# xns-ip67.net
KiCad netlist of a schematic drawn in EAGLE
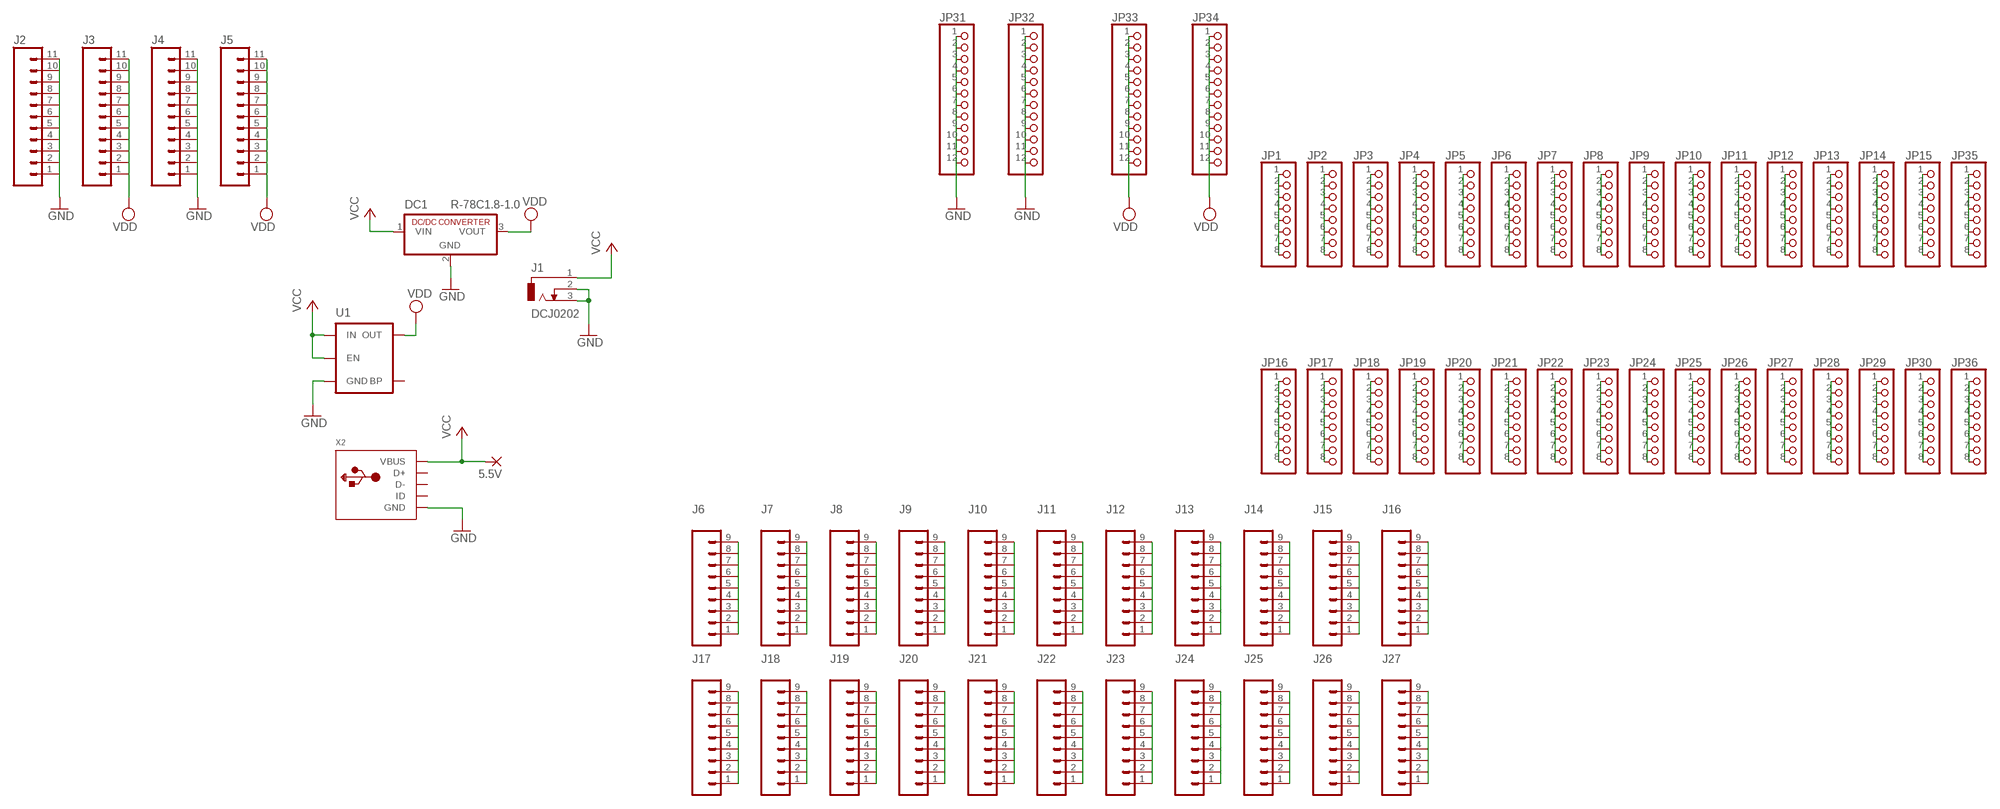
[diagram p0: schematic, sheet 1]

(export (version "E")
  (design (tool "Eeschema 10.0.6"))
  (components
    (comp (ref "5.5V")
      (value "WIREPAD1,6/0,9")
      (footprint "eagle-import:1,6_0,9")
      (libsource (lib "eagle-import") (part "WIREPAD1,6/0,9"))
    )
    (comp (ref "DC1")
      (value "R-78C1.8-1.0")
      (footprint "eagle-import:SIP3")
      (libsource (lib "eagle-import") (part "R-78C-1.01.8"))
    )
    (comp (ref "J1")
      (value "DCJ0202")
      (footprint "eagle-import:DCJ0202")
      (libsource (lib "eagle-import") (part "DCJ0202"))
    )
    (comp (ref "J2")
      (value "M111X11_NO_SILK")
      (footprint "eagle-import:1X11_NO_SILK")
      (libsource (lib "eagle-import") (part "M111X11_NO_SILK"))
    )
    (comp (ref "J3")
      (value "M111X11_NO_SILK")
      (footprint "eagle-import:1X11_NO_SILK")
      (libsource (lib "eagle-import") (part "M111X11_NO_SILK"))
    )
    (comp (ref "J4")
      (value "M111X11_NO_SILK")
      (footprint "eagle-import:1X11_NO_SILK")
      (libsource (lib "eagle-import") (part "M111X11_NO_SILK"))
    )
    (comp (ref "J5")
      (value "M111X11_NO_SILK")
      (footprint "eagle-import:1X11_NO_SILK")
      (libsource (lib "eagle-import") (part "M111X11_NO_SILK"))
    )
    (comp (ref "J6")
      (value "M09NO_SILK")
      (footprint "eagle-import:1X09_NO_SILK")
      (libsource (lib "eagle-import") (part "M09NO_SILK"))
    )
    (comp (ref "J7")
      (value "M09NO_SILK")
      (footprint "eagle-import:1X09_NO_SILK")
      (libsource (lib "eagle-import") (part "M09NO_SILK"))
    )
    (comp (ref "J8")
      (value "M09NO_SILK")
      (footprint "eagle-import:1X09_NO_SILK")
      (libsource (lib "eagle-import") (part "M09NO_SILK"))
    )
    (comp (ref "J9")
      (value "M09NO_SILK")
      (footprint "eagle-import:1X09_NO_SILK")
      (libsource (lib "eagle-import") (part "M09NO_SILK"))
    )
    (comp (ref "J10")
      (value "M09NO_SILK")
      (footprint "eagle-import:1X09_NO_SILK")
      (libsource (lib "eagle-import") (part "M09NO_SILK"))
    )
    (comp (ref "J11")
      (value "M09NO_SILK")
      (footprint "eagle-import:1X09_NO_SILK")
      (libsource (lib "eagle-import") (part "M09NO_SILK"))
    )
    (comp (ref "J12")
      (value "M09NO_SILK")
      (footprint "eagle-import:1X09_NO_SILK")
      (libsource (lib "eagle-import") (part "M09NO_SILK"))
    )
    (comp (ref "J13")
      (value "M09NO_SILK")
      (footprint "eagle-import:1X09_NO_SILK")
      (libsource (lib "eagle-import") (part "M09NO_SILK"))
    )
    (comp (ref "J14")
      (value "M09NO_SILK")
      (footprint "eagle-import:1X09_NO_SILK")
      (libsource (lib "eagle-import") (part "M09NO_SILK"))
    )
    (comp (ref "J15")
      (value "M09NO_SILK")
      (footprint "eagle-import:1X09_NO_SILK")
      (libsource (lib "eagle-import") (part "M09NO_SILK"))
    )
    (comp (ref "J16")
      (value "M09NO_SILK")
      (footprint "eagle-import:1X09_NO_SILK")
      (libsource (lib "eagle-import") (part "M09NO_SILK"))
    )
    (comp (ref "J17")
      (value "M09NO_SILK")
      (footprint "eagle-import:1X09_NO_SILK")
      (libsource (lib "eagle-import") (part "M09NO_SILK"))
    )
    (comp (ref "J18")
      (value "M09NO_SILK")
      (footprint "eagle-import:1X09_NO_SILK")
      (libsource (lib "eagle-import") (part "M09NO_SILK"))
    )
    (comp (ref "J19")
      (value "M09NO_SILK")
      (footprint "eagle-import:1X09_NO_SILK")
      (libsource (lib "eagle-import") (part "M09NO_SILK"))
    )
    (comp (ref "J20")
      (value "M09NO_SILK")
      (footprint "eagle-import:1X09_NO_SILK")
      (libsource (lib "eagle-import") (part "M09NO_SILK"))
    )
    (comp (ref "J21")
      (value "M09NO_SILK")
      (footprint "eagle-import:1X09_NO_SILK")
      (libsource (lib "eagle-import") (part "M09NO_SILK"))
    )
    (comp (ref "J22")
      (value "M09NO_SILK")
      (footprint "eagle-import:1X09_NO_SILK")
      (libsource (lib "eagle-import") (part "M09NO_SILK"))
    )
    (comp (ref "J23")
      (value "M09NO_SILK")
      (footprint "eagle-import:1X09_NO_SILK")
      (libsource (lib "eagle-import") (part "M09NO_SILK"))
    )
    (comp (ref "J24")
      (value "M09NO_SILK")
      (footprint "eagle-import:1X09_NO_SILK")
      (libsource (lib "eagle-import") (part "M09NO_SILK"))
    )
    (comp (ref "J25")
      (value "M09NO_SILK")
      (footprint "eagle-import:1X09_NO_SILK")
      (libsource (lib "eagle-import") (part "M09NO_SILK"))
    )
    (comp (ref "J26")
      (value "M09NO_SILK")
      (footprint "eagle-import:1X09_NO_SILK")
      (libsource (lib "eagle-import") (part "M09NO_SILK"))
    )
    (comp (ref "J27")
      (value "M09NO_SILK")
      (footprint "eagle-import:1X09_NO_SILK")
      (libsource (lib "eagle-import") (part "M09NO_SILK"))
    )
    (comp (ref "JP1")
      (value "PINHD-1X8CLEANBIG")
      (footprint "eagle-import:1X08-CLEANBIG")
      (libsource (lib "eagle-import") (part "PINHD-1X8CLEANBIG"))
    )
    (comp (ref "JP2")
      (value "PINHD-1X8CLEANBIG")
      (footprint "eagle-import:1X08-CLEANBIG")
      (libsource (lib "eagle-import") (part "PINHD-1X8CLEANBIG"))
    )
    (comp (ref "JP3")
      (value "PINHD-1X8CLEANBIG")
      (footprint "eagle-import:1X08-CLEANBIG")
      (libsource (lib "eagle-import") (part "PINHD-1X8CLEANBIG"))
    )
    (comp (ref "JP4")
      (value "PINHD-1X8CLEANBIG")
      (footprint "eagle-import:1X08-CLEANBIG")
      (libsource (lib "eagle-import") (part "PINHD-1X8CLEANBIG"))
    )
    (comp (ref "JP5")
      (value "PINHD-1X8CLEANBIG")
      (footprint "eagle-import:1X08-CLEANBIG")
      (libsource (lib "eagle-import") (part "PINHD-1X8CLEANBIG"))
    )
    (comp (ref "JP6")
      (value "PINHD-1X8CLEANBIG")
      (footprint "eagle-import:1X08-CLEANBIG")
      (libsource (lib "eagle-import") (part "PINHD-1X8CLEANBIG"))
    )
    (comp (ref "JP7")
      (value "PINHD-1X8CLEANBIG")
      (footprint "eagle-import:1X08-CLEANBIG")
      (libsource (lib "eagle-import") (part "PINHD-1X8CLEANBIG"))
    )
    (comp (ref "JP8")
      (value "PINHD-1X8CLEANBIG")
      (footprint "eagle-import:1X08-CLEANBIG")
      (libsource (lib "eagle-import") (part "PINHD-1X8CLEANBIG"))
    )
    (comp (ref "JP9")
      (value "PINHD-1X8CLEANBIG")
      (footprint "eagle-import:1X08-CLEANBIG")
      (libsource (lib "eagle-import") (part "PINHD-1X8CLEANBIG"))
    )
    (comp (ref "JP10")
      (value "PINHD-1X8CLEANBIG")
      (footprint "eagle-import:1X08-CLEANBIG")
      (libsource (lib "eagle-import") (part "PINHD-1X8CLEANBIG"))
    )
    (comp (ref "JP11")
      (value "PINHD-1X8CLEANBIG")
      (footprint "eagle-import:1X08-CLEANBIG")
      (libsource (lib "eagle-import") (part "PINHD-1X8CLEANBIG"))
    )
    (comp (ref "JP12")
      (value "PINHD-1X8CLEANBIG")
      (footprint "eagle-import:1X08-CLEANBIG")
      (libsource (lib "eagle-import") (part "PINHD-1X8CLEANBIG"))
    )
    (comp (ref "JP13")
      (value "PINHD-1X8CLEANBIG")
      (footprint "eagle-import:1X08-CLEANBIG")
      (libsource (lib "eagle-import") (part "PINHD-1X8CLEANBIG"))
    )
    (comp (ref "JP14")
      (value "PINHD-1X8CLEANBIG")
      (footprint "eagle-import:1X08-CLEANBIG")
      (libsource (lib "eagle-import") (part "PINHD-1X8CLEANBIG"))
    )
    (comp (ref "JP15")
      (value "PINHD-1X8CLEANBIG")
      (footprint "eagle-import:1X08-CLEANBIG")
      (libsource (lib "eagle-import") (part "PINHD-1X8CLEANBIG"))
    )
    (comp (ref "JP16")
      (value "PINHD-1X8CLEANBIG")
      (footprint "eagle-import:1X08-CLEANBIG")
      (libsource (lib "eagle-import") (part "PINHD-1X8CLEANBIG"))
    )
    (comp (ref "JP17")
      (value "PINHD-1X8CLEANBIG")
      (footprint "eagle-import:1X08-CLEANBIG")
      (libsource (lib "eagle-import") (part "PINHD-1X8CLEANBIG"))
    )
    (comp (ref "JP18")
      (value "PINHD-1X8CLEANBIG")
      (footprint "eagle-import:1X08-CLEANBIG")
      (libsource (lib "eagle-import") (part "PINHD-1X8CLEANBIG"))
    )
    (comp (ref "JP19")
      (value "PINHD-1X8CLEANBIG")
      (footprint "eagle-import:1X08-CLEANBIG")
      (libsource (lib "eagle-import") (part "PINHD-1X8CLEANBIG"))
    )
    (comp (ref "JP20")
      (value "PINHD-1X8CLEANBIG")
      (footprint "eagle-import:1X08-CLEANBIG")
      (libsource (lib "eagle-import") (part "PINHD-1X8CLEANBIG"))
    )
    (comp (ref "JP21")
      (value "PINHD-1X8CLEANBIG")
      (footprint "eagle-import:1X08-CLEANBIG")
      (libsource (lib "eagle-import") (part "PINHD-1X8CLEANBIG"))
    )
    (comp (ref "JP22")
      (value "PINHD-1X8CLEANBIG")
      (footprint "eagle-import:1X08-CLEANBIG")
      (libsource (lib "eagle-import") (part "PINHD-1X8CLEANBIG"))
    )
    (comp (ref "JP23")
      (value "PINHD-1X8CLEANBIG")
      (footprint "eagle-import:1X08-CLEANBIG")
      (libsource (lib "eagle-import") (part "PINHD-1X8CLEANBIG"))
    )
    (comp (ref "JP24")
      (value "PINHD-1X8CLEANBIG")
      (footprint "eagle-import:1X08-CLEANBIG")
      (libsource (lib "eagle-import") (part "PINHD-1X8CLEANBIG"))
    )
    (comp (ref "JP25")
      (value "PINHD-1X8CLEANBIG")
      (footprint "eagle-import:1X08-CLEANBIG")
      (libsource (lib "eagle-import") (part "PINHD-1X8CLEANBIG"))
    )
    (comp (ref "JP26")
      (value "PINHD-1X8CLEANBIG")
      (footprint "eagle-import:1X08-CLEANBIG")
      (libsource (lib "eagle-import") (part "PINHD-1X8CLEANBIG"))
    )
    (comp (ref "JP27")
      (value "PINHD-1X8CLEANBIG")
      (footprint "eagle-import:1X08-CLEANBIG")
      (libsource (lib "eagle-import") (part "PINHD-1X8CLEANBIG"))
    )
    (comp (ref "JP28")
      (value "PINHD-1X8CLEANBIG")
      (footprint "eagle-import:1X08-CLEANBIG")
      (libsource (lib "eagle-import") (part "PINHD-1X8CLEANBIG"))
    )
    (comp (ref "JP29")
      (value "PINHD-1X8CLEANBIG")
      (footprint "eagle-import:1X08-CLEANBIG")
      (libsource (lib "eagle-import") (part "PINHD-1X8CLEANBIG"))
    )
    (comp (ref "JP30")
      (value "PINHD-1X8CLEANBIG")
      (footprint "eagle-import:1X08-CLEANBIG")
      (libsource (lib "eagle-import") (part "PINHD-1X8CLEANBIG"))
    )
    (comp (ref "JP31")
      (value "HEADER-1X12")
      (footprint "eagle-import:1X12_ROUND")
      (libsource (lib "eagle-import") (part "HEADER-1X12"))
    )
    (comp (ref "JP32")
      (value "HEADER-1X12")
      (footprint "eagle-import:1X12_ROUND")
      (libsource (lib "eagle-import") (part "HEADER-1X12"))
    )
    (comp (ref "JP33")
      (value "HEADER-1X12")
      (footprint "eagle-import:1X12_ROUND")
      (libsource (lib "eagle-import") (part "HEADER-1X12"))
    )
    (comp (ref "JP34")
      (value "HEADER-1X12")
      (footprint "eagle-import:1X12_ROUND")
      (libsource (lib "eagle-import") (part "HEADER-1X12"))
    )
    (comp (ref "JP35")
      (value "PINHD-1X8CLEANBIG")
      (footprint "eagle-import:1X08-CLEANBIG")
      (libsource (lib "eagle-import") (part "PINHD-1X8CLEANBIG"))
    )
    (comp (ref "JP36")
      (value "PINHD-1X8CLEANBIG")
      (footprint "eagle-import:1X08-CLEANBIG")
      (libsource (lib "eagle-import") (part "PINHD-1X8CLEANBIG"))
    )
    (comp (ref "U1")
      (value "MIC52053.3V")
      (footprint "eagle-import:SOT23-5")
      (libsource (lib "eagle-import") (part "MIC52053.3V"))
    )
    (comp (ref "X2")
      (value "USBMICRO_20329")
      (footprint "eagle-import:4UCONN_20329")
      (libsource (lib "eagle-import") (part "USBMICRO_20329"))
    )
  )
  (nets
    (net (code "1") (name "GND") (class "Default")
      (node (ref "DC1") (pin "2") (pinfunction "GND_2") (pintype "passive"))
      (node (ref "J1") (pin "2") (pinfunction "2_2") (pintype "passive"))
      (node (ref "J1") (pin "3") (pinfunction "3_3") (pintype "passive"))
      (node (ref "J2") (pin "1") (pinfunction "1_1") (pintype "passive"))
      (node (ref "J2") (pin "10") (pinfunction "10_10") (pintype "passive"))
      (node (ref "J2") (pin "11") (pinfunction "11_11") (pintype "passive"))
      (node (ref "J2") (pin "2") (pinfunction "2_2") (pintype "passive"))
      (node (ref "J2") (pin "3") (pinfunction "3_3") (pintype "passive"))
      (node (ref "J2") (pin "4") (pinfunction "4_4") (pintype "passive"))
      (node (ref "J2") (pin "5") (pinfunction "5_5") (pintype "passive"))
      (node (ref "J2") (pin "6") (pinfunction "6_6") (pintype "passive"))
      (node (ref "J2") (pin "7") (pinfunction "7_7") (pintype "passive"))
      (node (ref "J2") (pin "8") (pinfunction "8_8") (pintype "passive"))
      (node (ref "J2") (pin "9") (pinfunction "9_9") (pintype "passive"))
      (node (ref "J4") (pin "1") (pinfunction "1_1") (pintype "passive"))
      (node (ref "J4") (pin "10") (pinfunction "10_10") (pintype "passive"))
      (node (ref "J4") (pin "11") (pinfunction "11_11") (pintype "passive"))
      (node (ref "J4") (pin "2") (pinfunction "2_2") (pintype "passive"))
      (node (ref "J4") (pin "3") (pinfunction "3_3") (pintype "passive"))
      (node (ref "J4") (pin "4") (pinfunction "4_4") (pintype "passive"))
      (node (ref "J4") (pin "5") (pinfunction "5_5") (pintype "passive"))
      (node (ref "J4") (pin "6") (pinfunction "6_6") (pintype "passive"))
      (node (ref "J4") (pin "7") (pinfunction "7_7") (pintype "passive"))
      (node (ref "J4") (pin "8") (pinfunction "8_8") (pintype "passive"))
      (node (ref "J4") (pin "9") (pinfunction "9_9") (pintype "passive"))
      (node (ref "JP31") (pin "1") (pinfunction "1_1") (pintype "passive"))
      (node (ref "JP31") (pin "10") (pinfunction "10_10") (pintype "passive"))
      (node (ref "JP31") (pin "11") (pinfunction "11_11") (pintype "passive"))
      (node (ref "JP31") (pin "12") (pinfunction "12_12") (pintype "passive"))
      (node (ref "JP31") (pin "2") (pinfunction "2_2") (pintype "passive"))
      (node (ref "JP31") (pin "3") (pinfunction "3_3") (pintype "passive"))
      (node (ref "JP31") (pin "4") (pinfunction "4_4") (pintype "passive"))
      (node (ref "JP31") (pin "5") (pinfunction "5_5") (pintype "passive"))
      (node (ref "JP31") (pin "6") (pinfunction "6_6") (pintype "passive"))
      (node (ref "JP31") (pin "7") (pinfunction "7_7") (pintype "passive"))
      (node (ref "JP31") (pin "8") (pinfunction "8_8") (pintype "passive"))
      (node (ref "JP31") (pin "9") (pinfunction "9_9") (pintype "passive"))
      (node (ref "JP32") (pin "1") (pinfunction "1_1") (pintype "passive"))
      (node (ref "JP32") (pin "10") (pinfunction "10_10") (pintype "passive"))
      (node (ref "JP32") (pin "11") (pinfunction "11_11") (pintype "passive"))
      (node (ref "JP32") (pin "12") (pinfunction "12_12") (pintype "passive"))
      (node (ref "JP32") (pin "2") (pinfunction "2_2") (pintype "passive"))
      (node (ref "JP32") (pin "3") (pinfunction "3_3") (pintype "passive"))
      (node (ref "JP32") (pin "4") (pinfunction "4_4") (pintype "passive"))
      (node (ref "JP32") (pin "5") (pinfunction "5_5") (pintype "passive"))
      (node (ref "JP32") (pin "6") (pinfunction "6_6") (pintype "passive"))
      (node (ref "JP32") (pin "7") (pinfunction "7_7") (pintype "passive"))
      (node (ref "JP32") (pin "8") (pinfunction "8_8") (pintype "passive"))
      (node (ref "JP32") (pin "9") (pinfunction "9_9") (pintype "passive"))
      (node (ref "U1") (pin "2") (pinfunction "GND_2") (pintype "input"))
      (node (ref "X2") (pin "BASE@1") (pinfunction "GND_BASE@1") (pintype "power_in"))
      (node (ref "X2") (pin "BASE@2") (pinfunction "GND_BASE@2") (pintype "power_in"))
      (node (ref "X2") (pin "GND") (pinfunction "GND_GND") (pintype "power_in"))
      (node (ref "X2") (pin "SPRT@1") (pinfunction "GND_SPRT@1") (pintype "power_in"))
      (node (ref "X2") (pin "SPRT@2") (pinfunction "GND_SPRT@2") (pintype "power_in"))
      (node (ref "X2") (pin "SPRT@3") (pinfunction "GND_SPRT@3") (pintype "power_in"))
      (node (ref "X2") (pin "SPRT@4") (pinfunction "GND_SPRT@4") (pintype "power_in"))
    )
    (net (code "2") (name "Net-(J6-Pad1)") (class "Default")
      (node (ref "J6") (pin "1") (pinfunction "1_1") (pintype "passive"))
      (node (ref "J6") (pin "2") (pinfunction "2_2") (pintype "passive"))
      (node (ref "J6") (pin "3") (pinfunction "3_3") (pintype "passive"))
      (node (ref "J6") (pin "4") (pinfunction "4_4") (pintype "passive"))
      (node (ref "J6") (pin "5") (pinfunction "5_5") (pintype "passive"))
      (node (ref "J6") (pin "6") (pinfunction "6_6") (pintype "passive"))
      (node (ref "J6") (pin "7") (pinfunction "7_7") (pintype "passive"))
      (node (ref "J6") (pin "8") (pinfunction "8_8") (pintype "passive"))
      (node (ref "J6") (pin "9") (pinfunction "9_9") (pintype "passive"))
    )
    (net (code "3") (name "Net-(J7-Pad1)") (class "Default")
      (node (ref "J7") (pin "1") (pinfunction "1_1") (pintype "passive"))
      (node (ref "J7") (pin "2") (pinfunction "2_2") (pintype "passive"))
      (node (ref "J7") (pin "3") (pinfunction "3_3") (pintype "passive"))
      (node (ref "J7") (pin "4") (pinfunction "4_4") (pintype "passive"))
      (node (ref "J7") (pin "5") (pinfunction "5_5") (pintype "passive"))
      (node (ref "J7") (pin "6") (pinfunction "6_6") (pintype "passive"))
      (node (ref "J7") (pin "7") (pinfunction "7_7") (pintype "passive"))
      (node (ref "J7") (pin "8") (pinfunction "8_8") (pintype "passive"))
      (node (ref "J7") (pin "9") (pinfunction "9_9") (pintype "passive"))
    )
    (net (code "4") (name "Net-(J8-Pad1)") (class "Default")
      (node (ref "J8") (pin "1") (pinfunction "1_1") (pintype "passive"))
      (node (ref "J8") (pin "2") (pinfunction "2_2") (pintype "passive"))
      (node (ref "J8") (pin "3") (pinfunction "3_3") (pintype "passive"))
      (node (ref "J8") (pin "4") (pinfunction "4_4") (pintype "passive"))
      (node (ref "J8") (pin "5") (pinfunction "5_5") (pintype "passive"))
      (node (ref "J8") (pin "6") (pinfunction "6_6") (pintype "passive"))
      (node (ref "J8") (pin "7") (pinfunction "7_7") (pintype "passive"))
      (node (ref "J8") (pin "8") (pinfunction "8_8") (pintype "passive"))
      (node (ref "J8") (pin "9") (pinfunction "9_9") (pintype "passive"))
    )
    (net (code "5") (name "Net-(J9-Pad1)") (class "Default")
      (node (ref "J9") (pin "1") (pinfunction "1_1") (pintype "passive"))
      (node (ref "J9") (pin "2") (pinfunction "2_2") (pintype "passive"))
      (node (ref "J9") (pin "3") (pinfunction "3_3") (pintype "passive"))
      (node (ref "J9") (pin "4") (pinfunction "4_4") (pintype "passive"))
      (node (ref "J9") (pin "5") (pinfunction "5_5") (pintype "passive"))
      (node (ref "J9") (pin "6") (pinfunction "6_6") (pintype "passive"))
      (node (ref "J9") (pin "7") (pinfunction "7_7") (pintype "passive"))
      (node (ref "J9") (pin "8") (pinfunction "8_8") (pintype "passive"))
      (node (ref "J9") (pin "9") (pinfunction "9_9") (pintype "passive"))
    )
    (net (code "6") (name "Net-(J10-Pad1)") (class "Default")
      (node (ref "J10") (pin "1") (pinfunction "1_1") (pintype "passive"))
      (node (ref "J10") (pin "2") (pinfunction "2_2") (pintype "passive"))
      (node (ref "J10") (pin "3") (pinfunction "3_3") (pintype "passive"))
      (node (ref "J10") (pin "4") (pinfunction "4_4") (pintype "passive"))
      (node (ref "J10") (pin "5") (pinfunction "5_5") (pintype "passive"))
      (node (ref "J10") (pin "6") (pinfunction "6_6") (pintype "passive"))
      (node (ref "J10") (pin "7") (pinfunction "7_7") (pintype "passive"))
      (node (ref "J10") (pin "8") (pinfunction "8_8") (pintype "passive"))
      (node (ref "J10") (pin "9") (pinfunction "9_9") (pintype "passive"))
    )
    (net (code "7") (name "Net-(J11-Pad1)") (class "Default")
      (node (ref "J11") (pin "1") (pinfunction "1_1") (pintype "passive"))
      (node (ref "J11") (pin "2") (pinfunction "2_2") (pintype "passive"))
      (node (ref "J11") (pin "3") (pinfunction "3_3") (pintype "passive"))
      (node (ref "J11") (pin "4") (pinfunction "4_4") (pintype "passive"))
      (node (ref "J11") (pin "5") (pinfunction "5_5") (pintype "passive"))
      (node (ref "J11") (pin "6") (pinfunction "6_6") (pintype "passive"))
      (node (ref "J11") (pin "7") (pinfunction "7_7") (pintype "passive"))
      (node (ref "J11") (pin "8") (pinfunction "8_8") (pintype "passive"))
      (node (ref "J11") (pin "9") (pinfunction "9_9") (pintype "passive"))
    )
    (net (code "8") (name "Net-(J12-Pad1)") (class "Default")
      (node (ref "J12") (pin "1") (pinfunction "1_1") (pintype "passive"))
      (node (ref "J12") (pin "2") (pinfunction "2_2") (pintype "passive"))
      (node (ref "J12") (pin "3") (pinfunction "3_3") (pintype "passive"))
      (node (ref "J12") (pin "4") (pinfunction "4_4") (pintype "passive"))
      (node (ref "J12") (pin "5") (pinfunction "5_5") (pintype "passive"))
      (node (ref "J12") (pin "6") (pinfunction "6_6") (pintype "passive"))
      (node (ref "J12") (pin "7") (pinfunction "7_7") (pintype "passive"))
      (node (ref "J12") (pin "8") (pinfunction "8_8") (pintype "passive"))
      (node (ref "J12") (pin "9") (pinfunction "9_9") (pintype "passive"))
    )
    (net (code "9") (name "Net-(J13-Pad1)") (class "Default")
      (node (ref "J13") (pin "1") (pinfunction "1_1") (pintype "passive"))
      (node (ref "J13") (pin "2") (pinfunction "2_2") (pintype "passive"))
      (node (ref "J13") (pin "3") (pinfunction "3_3") (pintype "passive"))
      (node (ref "J13") (pin "4") (pinfunction "4_4") (pintype "passive"))
      (node (ref "J13") (pin "5") (pinfunction "5_5") (pintype "passive"))
      (node (ref "J13") (pin "6") (pinfunction "6_6") (pintype "passive"))
      (node (ref "J13") (pin "7") (pinfunction "7_7") (pintype "passive"))
      (node (ref "J13") (pin "8") (pinfunction "8_8") (pintype "passive"))
      (node (ref "J13") (pin "9") (pinfunction "9_9") (pintype "passive"))
    )
    (net (code "10") (name "Net-(J14-Pad1)") (class "Default")
      (node (ref "J14") (pin "1") (pinfunction "1_1") (pintype "passive"))
      (node (ref "J14") (pin "2") (pinfunction "2_2") (pintype "passive"))
      (node (ref "J14") (pin "3") (pinfunction "3_3") (pintype "passive"))
      (node (ref "J14") (pin "4") (pinfunction "4_4") (pintype "passive"))
      (node (ref "J14") (pin "5") (pinfunction "5_5") (pintype "passive"))
      (node (ref "J14") (pin "6") (pinfunction "6_6") (pintype "passive"))
      (node (ref "J14") (pin "7") (pinfunction "7_7") (pintype "passive"))
      (node (ref "J14") (pin "8") (pinfunction "8_8") (pintype "passive"))
      (node (ref "J14") (pin "9") (pinfunction "9_9") (pintype "passive"))
    )
    (net (code "11") (name "Net-(J15-Pad1)") (class "Default")
      (node (ref "J15") (pin "1") (pinfunction "1_1") (pintype "passive"))
      (node (ref "J15") (pin "2") (pinfunction "2_2") (pintype "passive"))
      (node (ref "J15") (pin "3") (pinfunction "3_3") (pintype "passive"))
      (node (ref "J15") (pin "4") (pinfunction "4_4") (pintype "passive"))
      (node (ref "J15") (pin "5") (pinfunction "5_5") (pintype "passive"))
      (node (ref "J15") (pin "6") (pinfunction "6_6") (pintype "passive"))
      (node (ref "J15") (pin "7") (pinfunction "7_7") (pintype "passive"))
      (node (ref "J15") (pin "8") (pinfunction "8_8") (pintype "passive"))
      (node (ref "J15") (pin "9") (pinfunction "9_9") (pintype "passive"))
    )
    (net (code "12") (name "Net-(J16-Pad1)") (class "Default")
      (node (ref "J16") (pin "1") (pinfunction "1_1") (pintype "passive"))
      (node (ref "J16") (pin "2") (pinfunction "2_2") (pintype "passive"))
      (node (ref "J16") (pin "3") (pinfunction "3_3") (pintype "passive"))
      (node (ref "J16") (pin "4") (pinfunction "4_4") (pintype "passive"))
      (node (ref "J16") (pin "5") (pinfunction "5_5") (pintype "passive"))
      (node (ref "J16") (pin "6") (pinfunction "6_6") (pintype "passive"))
      (node (ref "J16") (pin "7") (pinfunction "7_7") (pintype "passive"))
      (node (ref "J16") (pin "8") (pinfunction "8_8") (pintype "passive"))
      (node (ref "J16") (pin "9") (pinfunction "9_9") (pintype "passive"))
    )
    (net (code "13") (name "Net-(J17-Pad1)") (class "Default")
      (node (ref "J17") (pin "1") (pinfunction "1_1") (pintype "passive"))
      (node (ref "J17") (pin "2") (pinfunction "2_2") (pintype "passive"))
      (node (ref "J17") (pin "3") (pinfunction "3_3") (pintype "passive"))
      (node (ref "J17") (pin "4") (pinfunction "4_4") (pintype "passive"))
      (node (ref "J17") (pin "5") (pinfunction "5_5") (pintype "passive"))
      (node (ref "J17") (pin "6") (pinfunction "6_6") (pintype "passive"))
      (node (ref "J17") (pin "7") (pinfunction "7_7") (pintype "passive"))
      (node (ref "J17") (pin "8") (pinfunction "8_8") (pintype "passive"))
      (node (ref "J17") (pin "9") (pinfunction "9_9") (pintype "passive"))
    )
    (net (code "14") (name "Net-(J18-Pad1)") (class "Default")
      (node (ref "J18") (pin "1") (pinfunction "1_1") (pintype "passive"))
      (node (ref "J18") (pin "2") (pinfunction "2_2") (pintype "passive"))
      (node (ref "J18") (pin "3") (pinfunction "3_3") (pintype "passive"))
      (node (ref "J18") (pin "4") (pinfunction "4_4") (pintype "passive"))
      (node (ref "J18") (pin "5") (pinfunction "5_5") (pintype "passive"))
      (node (ref "J18") (pin "6") (pinfunction "6_6") (pintype "passive"))
      (node (ref "J18") (pin "7") (pinfunction "7_7") (pintype "passive"))
      (node (ref "J18") (pin "8") (pinfunction "8_8") (pintype "passive"))
      (node (ref "J18") (pin "9") (pinfunction "9_9") (pintype "passive"))
    )
    (net (code "15") (name "Net-(J19-Pad1)") (class "Default")
      (node (ref "J19") (pin "1") (pinfunction "1_1") (pintype "passive"))
      (node (ref "J19") (pin "2") (pinfunction "2_2") (pintype "passive"))
      (node (ref "J19") (pin "3") (pinfunction "3_3") (pintype "passive"))
      (node (ref "J19") (pin "4") (pinfunction "4_4") (pintype "passive"))
      (node (ref "J19") (pin "5") (pinfunction "5_5") (pintype "passive"))
      (node (ref "J19") (pin "6") (pinfunction "6_6") (pintype "passive"))
      (node (ref "J19") (pin "7") (pinfunction "7_7") (pintype "passive"))
      (node (ref "J19") (pin "8") (pinfunction "8_8") (pintype "passive"))
      (node (ref "J19") (pin "9") (pinfunction "9_9") (pintype "passive"))
    )
    (net (code "16") (name "Net-(J20-Pad1)") (class "Default")
      (node (ref "J20") (pin "1") (pinfunction "1_1") (pintype "passive"))
      (node (ref "J20") (pin "2") (pinfunction "2_2") (pintype "passive"))
      (node (ref "J20") (pin "3") (pinfunction "3_3") (pintype "passive"))
      (node (ref "J20") (pin "4") (pinfunction "4_4") (pintype "passive"))
      (node (ref "J20") (pin "5") (pinfunction "5_5") (pintype "passive"))
      (node (ref "J20") (pin "6") (pinfunction "6_6") (pintype "passive"))
      (node (ref "J20") (pin "7") (pinfunction "7_7") (pintype "passive"))
      (node (ref "J20") (pin "8") (pinfunction "8_8") (pintype "passive"))
      (node (ref "J20") (pin "9") (pinfunction "9_9") (pintype "passive"))
    )
    (net (code "17") (name "Net-(J21-Pad1)") (class "Default")
      (node (ref "J21") (pin "1") (pinfunction "1_1") (pintype "passive"))
      (node (ref "J21") (pin "2") (pinfunction "2_2") (pintype "passive"))
      (node (ref "J21") (pin "3") (pinfunction "3_3") (pintype "passive"))
      (node (ref "J21") (pin "4") (pinfunction "4_4") (pintype "passive"))
      (node (ref "J21") (pin "5") (pinfunction "5_5") (pintype "passive"))
      (node (ref "J21") (pin "6") (pinfunction "6_6") (pintype "passive"))
      (node (ref "J21") (pin "7") (pinfunction "7_7") (pintype "passive"))
      (node (ref "J21") (pin "8") (pinfunction "8_8") (pintype "passive"))
      (node (ref "J21") (pin "9") (pinfunction "9_9") (pintype "passive"))
    )
    (net (code "18") (name "Net-(J22-Pad1)") (class "Default")
      (node (ref "J22") (pin "1") (pinfunction "1_1") (pintype "passive"))
      (node (ref "J22") (pin "2") (pinfunction "2_2") (pintype "passive"))
      (node (ref "J22") (pin "3") (pinfunction "3_3") (pintype "passive"))
      (node (ref "J22") (pin "4") (pinfunction "4_4") (pintype "passive"))
      (node (ref "J22") (pin "5") (pinfunction "5_5") (pintype "passive"))
      (node (ref "J22") (pin "6") (pinfunction "6_6") (pintype "passive"))
      (node (ref "J22") (pin "7") (pinfunction "7_7") (pintype "passive"))
      (node (ref "J22") (pin "8") (pinfunction "8_8") (pintype "passive"))
      (node (ref "J22") (pin "9") (pinfunction "9_9") (pintype "passive"))
    )
    (net (code "19") (name "Net-(J23-Pad1)") (class "Default")
      (node (ref "J23") (pin "1") (pinfunction "1_1") (pintype "passive"))
      (node (ref "J23") (pin "2") (pinfunction "2_2") (pintype "passive"))
      (node (ref "J23") (pin "3") (pinfunction "3_3") (pintype "passive"))
      (node (ref "J23") (pin "4") (pinfunction "4_4") (pintype "passive"))
      (node (ref "J23") (pin "5") (pinfunction "5_5") (pintype "passive"))
      (node (ref "J23") (pin "6") (pinfunction "6_6") (pintype "passive"))
      (node (ref "J23") (pin "7") (pinfunction "7_7") (pintype "passive"))
      (node (ref "J23") (pin "8") (pinfunction "8_8") (pintype "passive"))
      (node (ref "J23") (pin "9") (pinfunction "9_9") (pintype "passive"))
    )
    (net (code "20") (name "Net-(J24-Pad1)") (class "Default")
      (node (ref "J24") (pin "1") (pinfunction "1_1") (pintype "passive"))
      (node (ref "J24") (pin "2") (pinfunction "2_2") (pintype "passive"))
      (node (ref "J24") (pin "3") (pinfunction "3_3") (pintype "passive"))
      (node (ref "J24") (pin "4") (pinfunction "4_4") (pintype "passive"))
      (node (ref "J24") (pin "5") (pinfunction "5_5") (pintype "passive"))
      (node (ref "J24") (pin "6") (pinfunction "6_6") (pintype "passive"))
      (node (ref "J24") (pin "7") (pinfunction "7_7") (pintype "passive"))
      (node (ref "J24") (pin "8") (pinfunction "8_8") (pintype "passive"))
      (node (ref "J24") (pin "9") (pinfunction "9_9") (pintype "passive"))
    )
    (net (code "21") (name "Net-(J25-Pad1)") (class "Default")
      (node (ref "J25") (pin "1") (pinfunction "1_1") (pintype "passive"))
      (node (ref "J25") (pin "2") (pinfunction "2_2") (pintype "passive"))
      (node (ref "J25") (pin "3") (pinfunction "3_3") (pintype "passive"))
      (node (ref "J25") (pin "4") (pinfunction "4_4") (pintype "passive"))
      (node (ref "J25") (pin "5") (pinfunction "5_5") (pintype "passive"))
      (node (ref "J25") (pin "6") (pinfunction "6_6") (pintype "passive"))
      (node (ref "J25") (pin "7") (pinfunction "7_7") (pintype "passive"))
      (node (ref "J25") (pin "8") (pinfunction "8_8") (pintype "passive"))
      (node (ref "J25") (pin "9") (pinfunction "9_9") (pintype "passive"))
    )
    (net (code "22") (name "Net-(J26-Pad1)") (class "Default")
      (node (ref "J26") (pin "1") (pinfunction "1_1") (pintype "passive"))
      (node (ref "J26") (pin "2") (pinfunction "2_2") (pintype "passive"))
      (node (ref "J26") (pin "3") (pinfunction "3_3") (pintype "passive"))
      (node (ref "J26") (pin "4") (pinfunction "4_4") (pintype "passive"))
      (node (ref "J26") (pin "5") (pinfunction "5_5") (pintype "passive"))
      (node (ref "J26") (pin "6") (pinfunction "6_6") (pintype "passive"))
      (node (ref "J26") (pin "7") (pinfunction "7_7") (pintype "passive"))
      (node (ref "J26") (pin "8") (pinfunction "8_8") (pintype "passive"))
      (node (ref "J26") (pin "9") (pinfunction "9_9") (pintype "passive"))
    )
    (net (code "23") (name "Net-(J27-Pad1)") (class "Default")
      (node (ref "J27") (pin "1") (pinfunction "1_1") (pintype "passive"))
      (node (ref "J27") (pin "2") (pinfunction "2_2") (pintype "passive"))
      (node (ref "J27") (pin "3") (pinfunction "3_3") (pintype "passive"))
      (node (ref "J27") (pin "4") (pinfunction "4_4") (pintype "passive"))
      (node (ref "J27") (pin "5") (pinfunction "5_5") (pintype "passive"))
      (node (ref "J27") (pin "6") (pinfunction "6_6") (pintype "passive"))
      (node (ref "J27") (pin "7") (pinfunction "7_7") (pintype "passive"))
      (node (ref "J27") (pin "8") (pinfunction "8_8") (pintype "passive"))
      (node (ref "J27") (pin "9") (pinfunction "9_9") (pintype "passive"))
    )
    (net (code "24") (name "Net-(JP1-Pad1)") (class "Default")
      (node (ref "JP1") (pin "1") (pinfunction "1_1") (pintype "passive"))
      (node (ref "JP1") (pin "2") (pinfunction "2_2") (pintype "passive"))
      (node (ref "JP1") (pin "3") (pinfunction "3_3") (pintype "passive"))
      (node (ref "JP1") (pin "4") (pinfunction "4_4") (pintype "passive"))
      (node (ref "JP1") (pin "5") (pinfunction "5_5") (pintype "passive"))
      (node (ref "JP1") (pin "6") (pinfunction "6_6") (pintype "passive"))
      (node (ref "JP1") (pin "7") (pinfunction "7_7") (pintype "passive"))
      (node (ref "JP1") (pin "8") (pinfunction "8_8") (pintype "passive"))
    )
    (net (code "25") (name "Net-(JP2-Pad1)") (class "Default")
      (node (ref "JP2") (pin "1") (pinfunction "1_1") (pintype "passive"))
      (node (ref "JP2") (pin "2") (pinfunction "2_2") (pintype "passive"))
      (node (ref "JP2") (pin "3") (pinfunction "3_3") (pintype "passive"))
      (node (ref "JP2") (pin "4") (pinfunction "4_4") (pintype "passive"))
      (node (ref "JP2") (pin "5") (pinfunction "5_5") (pintype "passive"))
      (node (ref "JP2") (pin "6") (pinfunction "6_6") (pintype "passive"))
      (node (ref "JP2") (pin "7") (pinfunction "7_7") (pintype "passive"))
      (node (ref "JP2") (pin "8") (pinfunction "8_8") (pintype "passive"))
    )
    (net (code "26") (name "Net-(JP3-Pad1)") (class "Default")
      (node (ref "JP3") (pin "1") (pinfunction "1_1") (pintype "passive"))
      (node (ref "JP3") (pin "2") (pinfunction "2_2") (pintype "passive"))
      (node (ref "JP3") (pin "3") (pinfunction "3_3") (pintype "passive"))
      (node (ref "JP3") (pin "4") (pinfunction "4_4") (pintype "passive"))
      (node (ref "JP3") (pin "5") (pinfunction "5_5") (pintype "passive"))
      (node (ref "JP3") (pin "6") (pinfunction "6_6") (pintype "passive"))
      (node (ref "JP3") (pin "7") (pinfunction "7_7") (pintype "passive"))
      (node (ref "JP3") (pin "8") (pinfunction "8_8") (pintype "passive"))
    )
    (net (code "27") (name "Net-(JP4-Pad1)") (class "Default")
      (node (ref "JP4") (pin "1") (pinfunction "1_1") (pintype "passive"))
      (node (ref "JP4") (pin "2") (pinfunction "2_2") (pintype "passive"))
      (node (ref "JP4") (pin "3") (pinfunction "3_3") (pintype "passive"))
      (node (ref "JP4") (pin "4") (pinfunction "4_4") (pintype "passive"))
      (node (ref "JP4") (pin "5") (pinfunction "5_5") (pintype "passive"))
      (node (ref "JP4") (pin "6") (pinfunction "6_6") (pintype "passive"))
      (node (ref "JP4") (pin "7") (pinfunction "7_7") (pintype "passive"))
      (node (ref "JP4") (pin "8") (pinfunction "8_8") (pintype "passive"))
    )
    (net (code "28") (name "Net-(JP5-Pad1)") (class "Default")
      (node (ref "JP5") (pin "1") (pinfunction "1_1") (pintype "passive"))
      (node (ref "JP5") (pin "2") (pinfunction "2_2") (pintype "passive"))
      (node (ref "JP5") (pin "3") (pinfunction "3_3") (pintype "passive"))
      (node (ref "JP5") (pin "4") (pinfunction "4_4") (pintype "passive"))
      (node (ref "JP5") (pin "5") (pinfunction "5_5") (pintype "passive"))
      (node (ref "JP5") (pin "6") (pinfunction "6_6") (pintype "passive"))
      (node (ref "JP5") (pin "7") (pinfunction "7_7") (pintype "passive"))
      (node (ref "JP5") (pin "8") (pinfunction "8_8") (pintype "passive"))
    )
    (net (code "29") (name "Net-(JP6-Pad1)") (class "Default")
      (node (ref "JP6") (pin "1") (pinfunction "1_1") (pintype "passive"))
      (node (ref "JP6") (pin "2") (pinfunction "2_2") (pintype "passive"))
      (node (ref "JP6") (pin "3") (pinfunction "3_3") (pintype "passive"))
      (node (ref "JP6") (pin "4") (pinfunction "4_4") (pintype "passive"))
      (node (ref "JP6") (pin "5") (pinfunction "5_5") (pintype "passive"))
      (node (ref "JP6") (pin "6") (pinfunction "6_6") (pintype "passive"))
      (node (ref "JP6") (pin "7") (pinfunction "7_7") (pintype "passive"))
      (node (ref "JP6") (pin "8") (pinfunction "8_8") (pintype "passive"))
    )
    (net (code "30") (name "Net-(JP7-Pad1)") (class "Default")
      (node (ref "JP7") (pin "1") (pinfunction "1_1") (pintype "passive"))
      (node (ref "JP7") (pin "2") (pinfunction "2_2") (pintype "passive"))
      (node (ref "JP7") (pin "3") (pinfunction "3_3") (pintype "passive"))
      (node (ref "JP7") (pin "4") (pinfunction "4_4") (pintype "passive"))
      (node (ref "JP7") (pin "5") (pinfunction "5_5") (pintype "passive"))
      (node (ref "JP7") (pin "6") (pinfunction "6_6") (pintype "passive"))
      (node (ref "JP7") (pin "7") (pinfunction "7_7") (pintype "passive"))
      (node (ref "JP7") (pin "8") (pinfunction "8_8") (pintype "passive"))
    )
    (net (code "31") (name "Net-(JP8-Pad1)") (class "Default")
      (node (ref "JP8") (pin "1") (pinfunction "1_1") (pintype "passive"))
      (node (ref "JP8") (pin "2") (pinfunction "2_2") (pintype "passive"))
      (node (ref "JP8") (pin "3") (pinfunction "3_3") (pintype "passive"))
      (node (ref "JP8") (pin "4") (pinfunction "4_4") (pintype "passive"))
      (node (ref "JP8") (pin "5") (pinfunction "5_5") (pintype "passive"))
      (node (ref "JP8") (pin "6") (pinfunction "6_6") (pintype "passive"))
      (node (ref "JP8") (pin "7") (pinfunction "7_7") (pintype "passive"))
      (node (ref "JP8") (pin "8") (pinfunction "8_8") (pintype "passive"))
    )
    (net (code "32") (name "Net-(JP9-Pad1)") (class "Default")
      (node (ref "JP9") (pin "1") (pinfunction "1_1") (pintype "passive"))
      (node (ref "JP9") (pin "2") (pinfunction "2_2") (pintype "passive"))
      (node (ref "JP9") (pin "3") (pinfunction "3_3") (pintype "passive"))
      (node (ref "JP9") (pin "4") (pinfunction "4_4") (pintype "passive"))
      (node (ref "JP9") (pin "5") (pinfunction "5_5") (pintype "passive"))
      (node (ref "JP9") (pin "6") (pinfunction "6_6") (pintype "passive"))
      (node (ref "JP9") (pin "7") (pinfunction "7_7") (pintype "passive"))
      (node (ref "JP9") (pin "8") (pinfunction "8_8") (pintype "passive"))
    )
    (net (code "33") (name "Net-(JP10-Pad1)") (class "Default")
      (node (ref "JP10") (pin "1") (pinfunction "1_1") (pintype "passive"))
      (node (ref "JP10") (pin "2") (pinfunction "2_2") (pintype "passive"))
      (node (ref "JP10") (pin "3") (pinfunction "3_3") (pintype "passive"))
      (node (ref "JP10") (pin "4") (pinfunction "4_4") (pintype "passive"))
      (node (ref "JP10") (pin "5") (pinfunction "5_5") (pintype "passive"))
      (node (ref "JP10") (pin "6") (pinfunction "6_6") (pintype "passive"))
      (node (ref "JP10") (pin "7") (pinfunction "7_7") (pintype "passive"))
      (node (ref "JP10") (pin "8") (pinfunction "8_8") (pintype "passive"))
    )
    (net (code "34") (name "Net-(JP11-Pad1)") (class "Default")
      (node (ref "JP11") (pin "1") (pinfunction "1_1") (pintype "passive"))
      (node (ref "JP11") (pin "2") (pinfunction "2_2") (pintype "passive"))
      (node (ref "JP11") (pin "3") (pinfunction "3_3") (pintype "passive"))
      (node (ref "JP11") (pin "4") (pinfunction "4_4") (pintype "passive"))
      (node (ref "JP11") (pin "5") (pinfunction "5_5") (pintype "passive"))
      (node (ref "JP11") (pin "6") (pinfunction "6_6") (pintype "passive"))
      (node (ref "JP11") (pin "7") (pinfunction "7_7") (pintype "passive"))
      (node (ref "JP11") (pin "8") (pinfunction "8_8") (pintype "passive"))
    )
    (net (code "35") (name "Net-(JP12-Pad1)") (class "Default")
      (node (ref "JP12") (pin "1") (pinfunction "1_1") (pintype "passive"))
      (node (ref "JP12") (pin "2") (pinfunction "2_2") (pintype "passive"))
      (node (ref "JP12") (pin "3") (pinfunction "3_3") (pintype "passive"))
      (node (ref "JP12") (pin "4") (pinfunction "4_4") (pintype "passive"))
      (node (ref "JP12") (pin "5") (pinfunction "5_5") (pintype "passive"))
      (node (ref "JP12") (pin "6") (pinfunction "6_6") (pintype "passive"))
      (node (ref "JP12") (pin "7") (pinfunction "7_7") (pintype "passive"))
      (node (ref "JP12") (pin "8") (pinfunction "8_8") (pintype "passive"))
    )
    (net (code "36") (name "Net-(JP13-Pad1)") (class "Default")
      (node (ref "JP13") (pin "1") (pinfunction "1_1") (pintype "passive"))
      (node (ref "JP13") (pin "2") (pinfunction "2_2") (pintype "passive"))
      (node (ref "JP13") (pin "3") (pinfunction "3_3") (pintype "passive"))
      (node (ref "JP13") (pin "4") (pinfunction "4_4") (pintype "passive"))
      (node (ref "JP13") (pin "5") (pinfunction "5_5") (pintype "passive"))
      (node (ref "JP13") (pin "6") (pinfunction "6_6") (pintype "passive"))
      (node (ref "JP13") (pin "7") (pinfunction "7_7") (pintype "passive"))
      (node (ref "JP13") (pin "8") (pinfunction "8_8") (pintype "passive"))
    )
    (net (code "37") (name "Net-(JP14-Pad1)") (class "Default")
      (node (ref "JP14") (pin "1") (pinfunction "1_1") (pintype "passive"))
      (node (ref "JP14") (pin "2") (pinfunction "2_2") (pintype "passive"))
      (node (ref "JP14") (pin "3") (pinfunction "3_3") (pintype "passive"))
      (node (ref "JP14") (pin "4") (pinfunction "4_4") (pintype "passive"))
      (node (ref "JP14") (pin "5") (pinfunction "5_5") (pintype "passive"))
      (node (ref "JP14") (pin "6") (pinfunction "6_6") (pintype "passive"))
      (node (ref "JP14") (pin "7") (pinfunction "7_7") (pintype "passive"))
      (node (ref "JP14") (pin "8") (pinfunction "8_8") (pintype "passive"))
    )
    (net (code "38") (name "Net-(JP15-Pad1)") (class "Default")
      (node (ref "JP15") (pin "1") (pinfunction "1_1") (pintype "passive"))
      (node (ref "JP15") (pin "2") (pinfunction "2_2") (pintype "passive"))
      (node (ref "JP15") (pin "3") (pinfunction "3_3") (pintype "passive"))
      (node (ref "JP15") (pin "4") (pinfunction "4_4") (pintype "passive"))
      (node (ref "JP15") (pin "5") (pinfunction "5_5") (pintype "passive"))
      (node (ref "JP15") (pin "6") (pinfunction "6_6") (pintype "passive"))
      (node (ref "JP15") (pin "7") (pinfunction "7_7") (pintype "passive"))
      (node (ref "JP15") (pin "8") (pinfunction "8_8") (pintype "passive"))
    )
    (net (code "39") (name "Net-(JP16-Pad1)") (class "Default")
      (node (ref "JP16") (pin "1") (pinfunction "1_1") (pintype "passive"))
      (node (ref "JP16") (pin "2") (pinfunction "2_2") (pintype "passive"))
      (node (ref "JP16") (pin "3") (pinfunction "3_3") (pintype "passive"))
      (node (ref "JP16") (pin "4") (pinfunction "4_4") (pintype "passive"))
      (node (ref "JP16") (pin "5") (pinfunction "5_5") (pintype "passive"))
      (node (ref "JP16") (pin "6") (pinfunction "6_6") (pintype "passive"))
      (node (ref "JP16") (pin "7") (pinfunction "7_7") (pintype "passive"))
      (node (ref "JP16") (pin "8") (pinfunction "8_8") (pintype "passive"))
    )
    (net (code "40") (name "Net-(JP17-Pad1)") (class "Default")
      (node (ref "JP17") (pin "1") (pinfunction "1_1") (pintype "passive"))
      (node (ref "JP17") (pin "2") (pinfunction "2_2") (pintype "passive"))
      (node (ref "JP17") (pin "3") (pinfunction "3_3") (pintype "passive"))
      (node (ref "JP17") (pin "4") (pinfunction "4_4") (pintype "passive"))
      (node (ref "JP17") (pin "5") (pinfunction "5_5") (pintype "passive"))
      (node (ref "JP17") (pin "6") (pinfunction "6_6") (pintype "passive"))
      (node (ref "JP17") (pin "7") (pinfunction "7_7") (pintype "passive"))
      (node (ref "JP17") (pin "8") (pinfunction "8_8") (pintype "passive"))
    )
    (net (code "41") (name "Net-(JP18-Pad1)") (class "Default")
      (node (ref "JP18") (pin "1") (pinfunction "1_1") (pintype "passive"))
      (node (ref "JP18") (pin "2") (pinfunction "2_2") (pintype "passive"))
      (node (ref "JP18") (pin "3") (pinfunction "3_3") (pintype "passive"))
      (node (ref "JP18") (pin "4") (pinfunction "4_4") (pintype "passive"))
      (node (ref "JP18") (pin "5") (pinfunction "5_5") (pintype "passive"))
      (node (ref "JP18") (pin "6") (pinfunction "6_6") (pintype "passive"))
      (node (ref "JP18") (pin "7") (pinfunction "7_7") (pintype "passive"))
      (node (ref "JP18") (pin "8") (pinfunction "8_8") (pintype "passive"))
    )
    (net (code "42") (name "Net-(JP19-Pad1)") (class "Default")
      (node (ref "JP19") (pin "1") (pinfunction "1_1") (pintype "passive"))
      (node (ref "JP19") (pin "2") (pinfunction "2_2") (pintype "passive"))
      (node (ref "JP19") (pin "3") (pinfunction "3_3") (pintype "passive"))
      (node (ref "JP19") (pin "4") (pinfunction "4_4") (pintype "passive"))
      (node (ref "JP19") (pin "5") (pinfunction "5_5") (pintype "passive"))
      (node (ref "JP19") (pin "6") (pinfunction "6_6") (pintype "passive"))
      (node (ref "JP19") (pin "7") (pinfunction "7_7") (pintype "passive"))
      (node (ref "JP19") (pin "8") (pinfunction "8_8") (pintype "passive"))
    )
    (net (code "43") (name "Net-(JP20-Pad1)") (class "Default")
      (node (ref "JP20") (pin "1") (pinfunction "1_1") (pintype "passive"))
      (node (ref "JP20") (pin "2") (pinfunction "2_2") (pintype "passive"))
      (node (ref "JP20") (pin "3") (pinfunction "3_3") (pintype "passive"))
      (node (ref "JP20") (pin "4") (pinfunction "4_4") (pintype "passive"))
      (node (ref "JP20") (pin "5") (pinfunction "5_5") (pintype "passive"))
      (node (ref "JP20") (pin "6") (pinfunction "6_6") (pintype "passive"))
      (node (ref "JP20") (pin "7") (pinfunction "7_7") (pintype "passive"))
      (node (ref "JP20") (pin "8") (pinfunction "8_8") (pintype "passive"))
    )
    (net (code "44") (name "Net-(JP21-Pad1)") (class "Default")
      (node (ref "JP21") (pin "1") (pinfunction "1_1") (pintype "passive"))
      (node (ref "JP21") (pin "2") (pinfunction "2_2") (pintype "passive"))
      (node (ref "JP21") (pin "3") (pinfunction "3_3") (pintype "passive"))
      (node (ref "JP21") (pin "4") (pinfunction "4_4") (pintype "passive"))
      (node (ref "JP21") (pin "5") (pinfunction "5_5") (pintype "passive"))
      (node (ref "JP21") (pin "6") (pinfunction "6_6") (pintype "passive"))
      (node (ref "JP21") (pin "7") (pinfunction "7_7") (pintype "passive"))
      (node (ref "JP21") (pin "8") (pinfunction "8_8") (pintype "passive"))
    )
    (net (code "45") (name "Net-(JP22-Pad1)") (class "Default")
      (node (ref "JP22") (pin "1") (pinfunction "1_1") (pintype "passive"))
      (node (ref "JP22") (pin "2") (pinfunction "2_2") (pintype "passive"))
      (node (ref "JP22") (pin "3") (pinfunction "3_3") (pintype "passive"))
      (node (ref "JP22") (pin "4") (pinfunction "4_4") (pintype "passive"))
      (node (ref "JP22") (pin "5") (pinfunction "5_5") (pintype "passive"))
      (node (ref "JP22") (pin "6") (pinfunction "6_6") (pintype "passive"))
      (node (ref "JP22") (pin "7") (pinfunction "7_7") (pintype "passive"))
      (node (ref "JP22") (pin "8") (pinfunction "8_8") (pintype "passive"))
    )
    (net (code "46") (name "Net-(JP23-Pad1)") (class "Default")
      (node (ref "JP23") (pin "1") (pinfunction "1_1") (pintype "passive"))
      (node (ref "JP23") (pin "2") (pinfunction "2_2") (pintype "passive"))
      (node (ref "JP23") (pin "3") (pinfunction "3_3") (pintype "passive"))
      (node (ref "JP23") (pin "4") (pinfunction "4_4") (pintype "passive"))
      (node (ref "JP23") (pin "5") (pinfunction "5_5") (pintype "passive"))
      (node (ref "JP23") (pin "6") (pinfunction "6_6") (pintype "passive"))
      (node (ref "JP23") (pin "7") (pinfunction "7_7") (pintype "passive"))
      (node (ref "JP23") (pin "8") (pinfunction "8_8") (pintype "passive"))
    )
    (net (code "47") (name "Net-(JP24-Pad1)") (class "Default")
      (node (ref "JP24") (pin "1") (pinfunction "1_1") (pintype "passive"))
      (node (ref "JP24") (pin "2") (pinfunction "2_2") (pintype "passive"))
      (node (ref "JP24") (pin "3") (pinfunction "3_3") (pintype "passive"))
      (node (ref "JP24") (pin "4") (pinfunction "4_4") (pintype "passive"))
      (node (ref "JP24") (pin "5") (pinfunction "5_5") (pintype "passive"))
      (node (ref "JP24") (pin "6") (pinfunction "6_6") (pintype "passive"))
      (node (ref "JP24") (pin "7") (pinfunction "7_7") (pintype "passive"))
      (node (ref "JP24") (pin "8") (pinfunction "8_8") (pintype "passive"))
    )
    (net (code "48") (name "Net-(JP25-Pad1)") (class "Default")
      (node (ref "JP25") (pin "1") (pinfunction "1_1") (pintype "passive"))
      (node (ref "JP25") (pin "2") (pinfunction "2_2") (pintype "passive"))
      (node (ref "JP25") (pin "3") (pinfunction "3_3") (pintype "passive"))
      (node (ref "JP25") (pin "4") (pinfunction "4_4") (pintype "passive"))
      (node (ref "JP25") (pin "5") (pinfunction "5_5") (pintype "passive"))
      (node (ref "JP25") (pin "6") (pinfunction "6_6") (pintype "passive"))
      (node (ref "JP25") (pin "7") (pinfunction "7_7") (pintype "passive"))
      (node (ref "JP25") (pin "8") (pinfunction "8_8") (pintype "passive"))
    )
    (net (code "49") (name "Net-(JP26-Pad1)") (class "Default")
      (node (ref "JP26") (pin "1") (pinfunction "1_1") (pintype "passive"))
      (node (ref "JP26") (pin "2") (pinfunction "2_2") (pintype "passive"))
      (node (ref "JP26") (pin "3") (pinfunction "3_3") (pintype "passive"))
      (node (ref "JP26") (pin "4") (pinfunction "4_4") (pintype "passive"))
      (node (ref "JP26") (pin "5") (pinfunction "5_5") (pintype "passive"))
      (node (ref "JP26") (pin "6") (pinfunction "6_6") (pintype "passive"))
      (node (ref "JP26") (pin "7") (pinfunction "7_7") (pintype "passive"))
      (node (ref "JP26") (pin "8") (pinfunction "8_8") (pintype "passive"))
    )
    (net (code "50") (name "Net-(JP27-Pad1)") (class "Default")
      (node (ref "JP27") (pin "1") (pinfunction "1_1") (pintype "passive"))
      (node (ref "JP27") (pin "2") (pinfunction "2_2") (pintype "passive"))
      (node (ref "JP27") (pin "3") (pinfunction "3_3") (pintype "passive"))
      (node (ref "JP27") (pin "4") (pinfunction "4_4") (pintype "passive"))
      (node (ref "JP27") (pin "5") (pinfunction "5_5") (pintype "passive"))
      (node (ref "JP27") (pin "6") (pinfunction "6_6") (pintype "passive"))
      (node (ref "JP27") (pin "7") (pinfunction "7_7") (pintype "passive"))
      (node (ref "JP27") (pin "8") (pinfunction "8_8") (pintype "passive"))
    )
    (net (code "51") (name "Net-(JP28-Pad1)") (class "Default")
      (node (ref "JP28") (pin "1") (pinfunction "1_1") (pintype "passive"))
      (node (ref "JP28") (pin "2") (pinfunction "2_2") (pintype "passive"))
      (node (ref "JP28") (pin "3") (pinfunction "3_3") (pintype "passive"))
      (node (ref "JP28") (pin "4") (pinfunction "4_4") (pintype "passive"))
      (node (ref "JP28") (pin "5") (pinfunction "5_5") (pintype "passive"))
      (node (ref "JP28") (pin "6") (pinfunction "6_6") (pintype "passive"))
      (node (ref "JP28") (pin "7") (pinfunction "7_7") (pintype "passive"))
      (node (ref "JP28") (pin "8") (pinfunction "8_8") (pintype "passive"))
    )
    (net (code "52") (name "Net-(JP29-Pad1)") (class "Default")
      (node (ref "JP29") (pin "1") (pinfunction "1_1") (pintype "passive"))
      (node (ref "JP29") (pin "2") (pinfunction "2_2") (pintype "passive"))
      (node (ref "JP29") (pin "3") (pinfunction "3_3") (pintype "passive"))
      (node (ref "JP29") (pin "4") (pinfunction "4_4") (pintype "passive"))
      (node (ref "JP29") (pin "5") (pinfunction "5_5") (pintype "passive"))
      (node (ref "JP29") (pin "6") (pinfunction "6_6") (pintype "passive"))
      (node (ref "JP29") (pin "7") (pinfunction "7_7") (pintype "passive"))
      (node (ref "JP29") (pin "8") (pinfunction "8_8") (pintype "passive"))
    )
    (net (code "53") (name "Net-(JP30-Pad1)") (class "Default")
      (node (ref "JP30") (pin "1") (pinfunction "1_1") (pintype "passive"))
      (node (ref "JP30") (pin "2") (pinfunction "2_2") (pintype "passive"))
      (node (ref "JP30") (pin "3") (pinfunction "3_3") (pintype "passive"))
      (node (ref "JP30") (pin "4") (pinfunction "4_4") (pintype "passive"))
      (node (ref "JP30") (pin "5") (pinfunction "5_5") (pintype "passive"))
      (node (ref "JP30") (pin "6") (pinfunction "6_6") (pintype "passive"))
      (node (ref "JP30") (pin "7") (pinfunction "7_7") (pintype "passive"))
      (node (ref "JP30") (pin "8") (pinfunction "8_8") (pintype "passive"))
    )
    (net (code "54") (name "Net-(JP35-Pad1)") (class "Default")
      (node (ref "JP35") (pin "1") (pinfunction "1_1") (pintype "passive"))
      (node (ref "JP35") (pin "2") (pinfunction "2_2") (pintype "passive"))
      (node (ref "JP35") (pin "3") (pinfunction "3_3") (pintype "passive"))
      (node (ref "JP35") (pin "4") (pinfunction "4_4") (pintype "passive"))
      (node (ref "JP35") (pin "5") (pinfunction "5_5") (pintype "passive"))
      (node (ref "JP35") (pin "6") (pinfunction "6_6") (pintype "passive"))
      (node (ref "JP35") (pin "7") (pinfunction "7_7") (pintype "passive"))
      (node (ref "JP35") (pin "8") (pinfunction "8_8") (pintype "passive"))
    )
    (net (code "55") (name "Net-(JP36-Pad1)") (class "Default")
      (node (ref "JP36") (pin "1") (pinfunction "1_1") (pintype "passive"))
      (node (ref "JP36") (pin "2") (pinfunction "2_2") (pintype "passive"))
      (node (ref "JP36") (pin "3") (pinfunction "3_3") (pintype "passive"))
      (node (ref "JP36") (pin "4") (pinfunction "4_4") (pintype "passive"))
      (node (ref "JP36") (pin "5") (pinfunction "5_5") (pintype "passive"))
      (node (ref "JP36") (pin "6") (pinfunction "6_6") (pintype "passive"))
      (node (ref "JP36") (pin "7") (pinfunction "7_7") (pintype "passive"))
      (node (ref "JP36") (pin "8") (pinfunction "8_8") (pintype "passive"))
    )
    (net (code "56") (name "VCC") (class "Default")
      (node (ref "5.5V") (pin "1") (pinfunction "P_1") (pintype "passive"))
      (node (ref "DC1") (pin "1") (pinfunction "VIN_1") (pintype "passive"))
      (node (ref "J1") (pin "1") (pinfunction "1_1") (pintype "passive"))
      (node (ref "U1") (pin "1") (pinfunction "IN_1") (pintype "input"))
      (node (ref "U1") (pin "3") (pinfunction "EN_3") (pintype "input"))
      (node (ref "X2") (pin "VBUS") (pinfunction "VBUS_VBUS") (pintype "power_in"))
    )
    (net (code "57") (name "VDD") (class "Default")
      (node (ref "DC1") (pin "3") (pinfunction "VOUT_3") (pintype "passive"))
      (node (ref "J3") (pin "1") (pinfunction "1_1") (pintype "passive"))
      (node (ref "J3") (pin "10") (pinfunction "10_10") (pintype "passive"))
      (node (ref "J3") (pin "11") (pinfunction "11_11") (pintype "passive"))
      (node (ref "J3") (pin "2") (pinfunction "2_2") (pintype "passive"))
      (node (ref "J3") (pin "3") (pinfunction "3_3") (pintype "passive"))
      (node (ref "J3") (pin "4") (pinfunction "4_4") (pintype "passive"))
      (node (ref "J3") (pin "5") (pinfunction "5_5") (pintype "passive"))
      (node (ref "J3") (pin "6") (pinfunction "6_6") (pintype "passive"))
      (node (ref "J3") (pin "7") (pinfunction "7_7") (pintype "passive"))
      (node (ref "J3") (pin "8") (pinfunction "8_8") (pintype "passive"))
      (node (ref "J3") (pin "9") (pinfunction "9_9") (pintype "passive"))
      (node (ref "J5") (pin "1") (pinfunction "1_1") (pintype "passive"))
      (node (ref "J5") (pin "10") (pinfunction "10_10") (pintype "passive"))
      (node (ref "J5") (pin "11") (pinfunction "11_11") (pintype "passive"))
      (node (ref "J5") (pin "2") (pinfunction "2_2") (pintype "passive"))
      (node (ref "J5") (pin "3") (pinfunction "3_3") (pintype "passive"))
      (node (ref "J5") (pin "4") (pinfunction "4_4") (pintype "passive"))
      (node (ref "J5") (pin "5") (pinfunction "5_5") (pintype "passive"))
      (node (ref "J5") (pin "6") (pinfunction "6_6") (pintype "passive"))
      (node (ref "J5") (pin "7") (pinfunction "7_7") (pintype "passive"))
      (node (ref "J5") (pin "8") (pinfunction "8_8") (pintype "passive"))
      (node (ref "J5") (pin "9") (pinfunction "9_9") (pintype "passive"))
      (node (ref "JP33") (pin "1") (pinfunction "1_1") (pintype "passive"))
      (node (ref "JP33") (pin "10") (pinfunction "10_10") (pintype "passive"))
      (node (ref "JP33") (pin "11") (pinfunction "11_11") (pintype "passive"))
      (node (ref "JP33") (pin "12") (pinfunction "12_12") (pintype "passive"))
      (node (ref "JP33") (pin "2") (pinfunction "2_2") (pintype "passive"))
      (node (ref "JP33") (pin "3") (pinfunction "3_3") (pintype "passive"))
      (node (ref "JP33") (pin "4") (pinfunction "4_4") (pintype "passive"))
      (node (ref "JP33") (pin "5") (pinfunction "5_5") (pintype "passive"))
      (node (ref "JP33") (pin "6") (pinfunction "6_6") (pintype "passive"))
      (node (ref "JP33") (pin "7") (pinfunction "7_7") (pintype "passive"))
      (node (ref "JP33") (pin "8") (pinfunction "8_8") (pintype "passive"))
      (node (ref "JP33") (pin "9") (pinfunction "9_9") (pintype "passive"))
      (node (ref "JP34") (pin "1") (pinfunction "1_1") (pintype "passive"))
      (node (ref "JP34") (pin "10") (pinfunction "10_10") (pintype "passive"))
      (node (ref "JP34") (pin "11") (pinfunction "11_11") (pintype "passive"))
      (node (ref "JP34") (pin "12") (pinfunction "12_12") (pintype "passive"))
      (node (ref "JP34") (pin "2") (pinfunction "2_2") (pintype "passive"))
      (node (ref "JP34") (pin "3") (pinfunction "3_3") (pintype "passive"))
      (node (ref "JP34") (pin "4") (pinfunction "4_4") (pintype "passive"))
      (node (ref "JP34") (pin "5") (pinfunction "5_5") (pintype "passive"))
      (node (ref "JP34") (pin "6") (pinfunction "6_6") (pintype "passive"))
      (node (ref "JP34") (pin "7") (pinfunction "7_7") (pintype "passive"))
      (node (ref "JP34") (pin "8") (pinfunction "8_8") (pintype "passive"))
      (node (ref "JP34") (pin "9") (pinfunction "9_9") (pintype "passive"))
      (node (ref "U1") (pin "5") (pinfunction "OUT_5") (pintype "passive"))
    )
    (net (code "58") (name "unconnected-(U1-BP-Pad4)") (class "Default")
      (node (ref "U1") (pin "4") (pinfunction "BP_4") (pintype "input"))
    )
    (net (code "59") (name "unconnected-(X2-PadD+)") (class "Default")
      (node (ref "X2") (pin "D+") (pinfunction "D+_D+") (pintype "bidirectional"))
    )
    (net (code "60") (name "unconnected-(X2-PadD-)") (class "Default")
      (node (ref "X2") (pin "D-") (pinfunction "D-_D-") (pintype "bidirectional"))
    )
    (net (code "61") (name "unconnected-(X2-PadID)") (class "Default")
      (node (ref "X2") (pin "ID") (pinfunction "ID_ID") (pintype "bidirectional"))
    )
  )
)
